# main.net
KiCad netlist of a schematic drawn in EAGLE
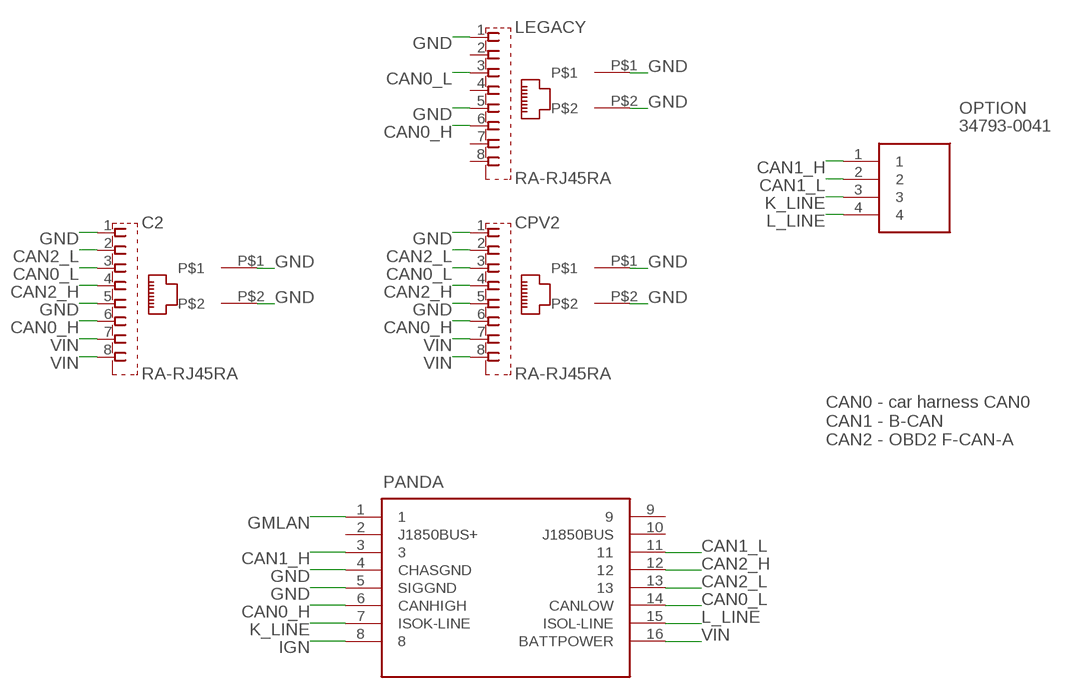
[diagram p0: schematic, sheet 1]

(export (version "E")
  (design (tool "Eeschema 10.0.6"))
  (components
    (comp (ref "C2")
      (value "RA-RJ45RA")
      (footprint "eagle-import:RA-RJ45")
      (libsource (lib "eagle-import") (part "RA-RJ45RA"))
    )
    (comp (ref "CPV2")
      (value "RA-RJ45RA")
      (footprint "eagle-import:RA-RJ45")
      (libsource (lib "eagle-import") (part "RA-RJ45RA"))
    )
    (comp (ref "LEGACY")
      (value "RA-RJ45RA")
      (footprint "eagle-import:RA-RJ45")
      (libsource (lib "eagle-import") (part "RA-RJ45RA"))
    )
    (comp (ref "OPTION")
      (value "34793-0041")
      (footprint "eagle-import:347930041")
      (fields (field (name "MOUSER_PART_NUMBER") "538-34793-0041"))
      (libsource (lib "eagle-import") (part "34793-0041"))
    )
    (comp (ref "PANDA")
      (value "OBDII-FEMALEFEMALE")
      (footprint "eagle-import:OBDII-FEMALE")
      (libsource (lib "eagle-import") (part "OBDII-FEMALEFEMALE"))
    )
  )
  (nets
    (net (code "1") (name "/CAN0_H") (class "Default")
      (node (ref "C2") (pin "6") (pinfunction "6_6") (pintype "passive"))
      (node (ref "CPV2") (pin "6") (pinfunction "6_6") (pintype "passive"))
      (node (ref "LEGACY") (pin "6") (pinfunction "6_6") (pintype "passive"))
      (node (ref "PANDA") (pin "6") (pinfunction "CANHIGH_6") (pintype "bidirectional"))
    )
    (net (code "2") (name "/CAN0_L") (class "Default")
      (node (ref "C2") (pin "3") (pinfunction "3_3") (pintype "passive"))
      (node (ref "CPV2") (pin "3") (pinfunction "3_3") (pintype "passive"))
      (node (ref "LEGACY") (pin "3") (pinfunction "3_3") (pintype "passive"))
      (node (ref "PANDA") (pin "14") (pinfunction "CANLOW_14") (pintype "bidirectional"))
    )
    (net (code "3") (name "/CAN1_H") (class "Default")
      (node (ref "OPTION") (pin "1") (pinfunction "1_1") (pintype "bidirectional"))
      (node (ref "PANDA") (pin "3") (pinfunction "3_3") (pintype "bidirectional"))
    )
    (net (code "4") (name "/CAN1_L") (class "Default")
      (node (ref "OPTION") (pin "2") (pinfunction "2_2") (pintype "bidirectional"))
      (node (ref "PANDA") (pin "11") (pinfunction "11_11") (pintype "bidirectional"))
    )
    (net (code "5") (name "/CAN2_H") (class "Default")
      (node (ref "C2") (pin "4") (pinfunction "4_4") (pintype "passive"))
      (node (ref "CPV2") (pin "4") (pinfunction "4_4") (pintype "passive"))
      (node (ref "PANDA") (pin "12") (pinfunction "12_12") (pintype "bidirectional"))
    )
    (net (code "6") (name "/CAN2_L") (class "Default")
      (node (ref "C2") (pin "2") (pinfunction "2_2") (pintype "passive"))
      (node (ref "CPV2") (pin "2") (pinfunction "2_2") (pintype "passive"))
      (node (ref "PANDA") (pin "13") (pinfunction "13_13") (pintype "bidirectional"))
    )
    (net (code "7") (name "/GMLAN") (class "Default")
      (node (ref "PANDA") (pin "1") (pinfunction "1_1") (pintype "bidirectional"))
    )
    (net (code "8") (name "/GND") (class "Default")
      (node (ref "C2") (pin "1") (pinfunction "1_1") (pintype "passive"))
      (node (ref "C2") (pin "5") (pinfunction "5_5") (pintype "passive"))
      (node (ref "C2") (pin "P$1") (pinfunction "P$1_P$1") (pintype "bidirectional"))
      (node (ref "C2") (pin "P$2") (pinfunction "P$2_P$2") (pintype "bidirectional"))
      (node (ref "CPV2") (pin "1") (pinfunction "1_1") (pintype "passive"))
      (node (ref "CPV2") (pin "5") (pinfunction "5_5") (pintype "passive"))
      (node (ref "CPV2") (pin "P$1") (pinfunction "P$1_P$1") (pintype "bidirectional"))
      (node (ref "CPV2") (pin "P$2") (pinfunction "P$2_P$2") (pintype "bidirectional"))
      (node (ref "LEGACY") (pin "1") (pinfunction "1_1") (pintype "passive"))
      (node (ref "LEGACY") (pin "5") (pinfunction "5_5") (pintype "passive"))
      (node (ref "LEGACY") (pin "P$1") (pinfunction "P$1_P$1") (pintype "bidirectional"))
      (node (ref "LEGACY") (pin "P$2") (pinfunction "P$2_P$2") (pintype "bidirectional"))
      (node (ref "PANDA") (pin "4") (pinfunction "CHASGND_4") (pintype "bidirectional"))
      (node (ref "PANDA") (pin "5") (pinfunction "SIGGND_5") (pintype "bidirectional"))
    )
    (net (code "9") (name "/IGN") (class "Default")
      (node (ref "PANDA") (pin "8") (pinfunction "8_8") (pintype "bidirectional"))
    )
    (net (code "10") (name "/K_LINE") (class "Default")
      (node (ref "OPTION") (pin "3") (pinfunction "3_3") (pintype "bidirectional"))
      (node (ref "PANDA") (pin "7") (pinfunction "ISOK-LINE_7") (pintype "bidirectional"))
    )
    (net (code "11") (name "/L_LINE") (class "Default")
      (node (ref "OPTION") (pin "4") (pinfunction "4_4") (pintype "bidirectional"))
      (node (ref "PANDA") (pin "15") (pinfunction "ISOL-LINE_15") (pintype "bidirectional"))
    )
    (net (code "12") (name "/VIN") (class "Default")
      (node (ref "C2") (pin "7") (pinfunction "7_7") (pintype "passive"))
      (node (ref "C2") (pin "8") (pinfunction "8_8") (pintype "passive"))
      (node (ref "CPV2") (pin "7") (pinfunction "7_7") (pintype "passive"))
      (node (ref "CPV2") (pin "8") (pinfunction "8_8") (pintype "passive"))
      (node (ref "PANDA") (pin "16") (pinfunction "BATTPOWER_16") (pintype "bidirectional"))
    )
    (net (code "13") (name "unconnected-(LEGACY-Pad2)") (class "Default")
      (node (ref "LEGACY") (pin "2") (pinfunction "2_2") (pintype "passive"))
    )
    (net (code "14") (name "unconnected-(LEGACY-Pad4)") (class "Default")
      (node (ref "LEGACY") (pin "4") (pinfunction "4_4") (pintype "passive"))
    )
    (net (code "15") (name "unconnected-(LEGACY-Pad7)") (class "Default")
      (node (ref "LEGACY") (pin "7") (pinfunction "7_7") (pintype "passive"))
    )
    (net (code "16") (name "unconnected-(LEGACY-Pad8)") (class "Default")
      (node (ref "LEGACY") (pin "8") (pinfunction "8_8") (pintype "passive"))
    )
    (net (code "17") (name "unconnected-(PANDA-J1850BUS+-Pad2)") (class "Default")
      (node (ref "PANDA") (pin "2") (pinfunction "J1850BUS+_2") (pintype "bidirectional"))
    )
    (net (code "18") (name "unconnected-(PANDA-J1850BUS-Pad10)") (class "Default")
      (node (ref "PANDA") (pin "10") (pinfunction "J1850BUS_10") (pintype "bidirectional"))
    )
    (net (code "19") (name "unconnected-(PANDA-Pad9)") (class "Default")
      (node (ref "PANDA") (pin "9") (pinfunction "9_9") (pintype "bidirectional"))
    )
  )
)
